# PSPS_AVNC_SRD_central-2020-10-21_FABRICA.net
KiCad netlist of a schematic drawn in EAGLE
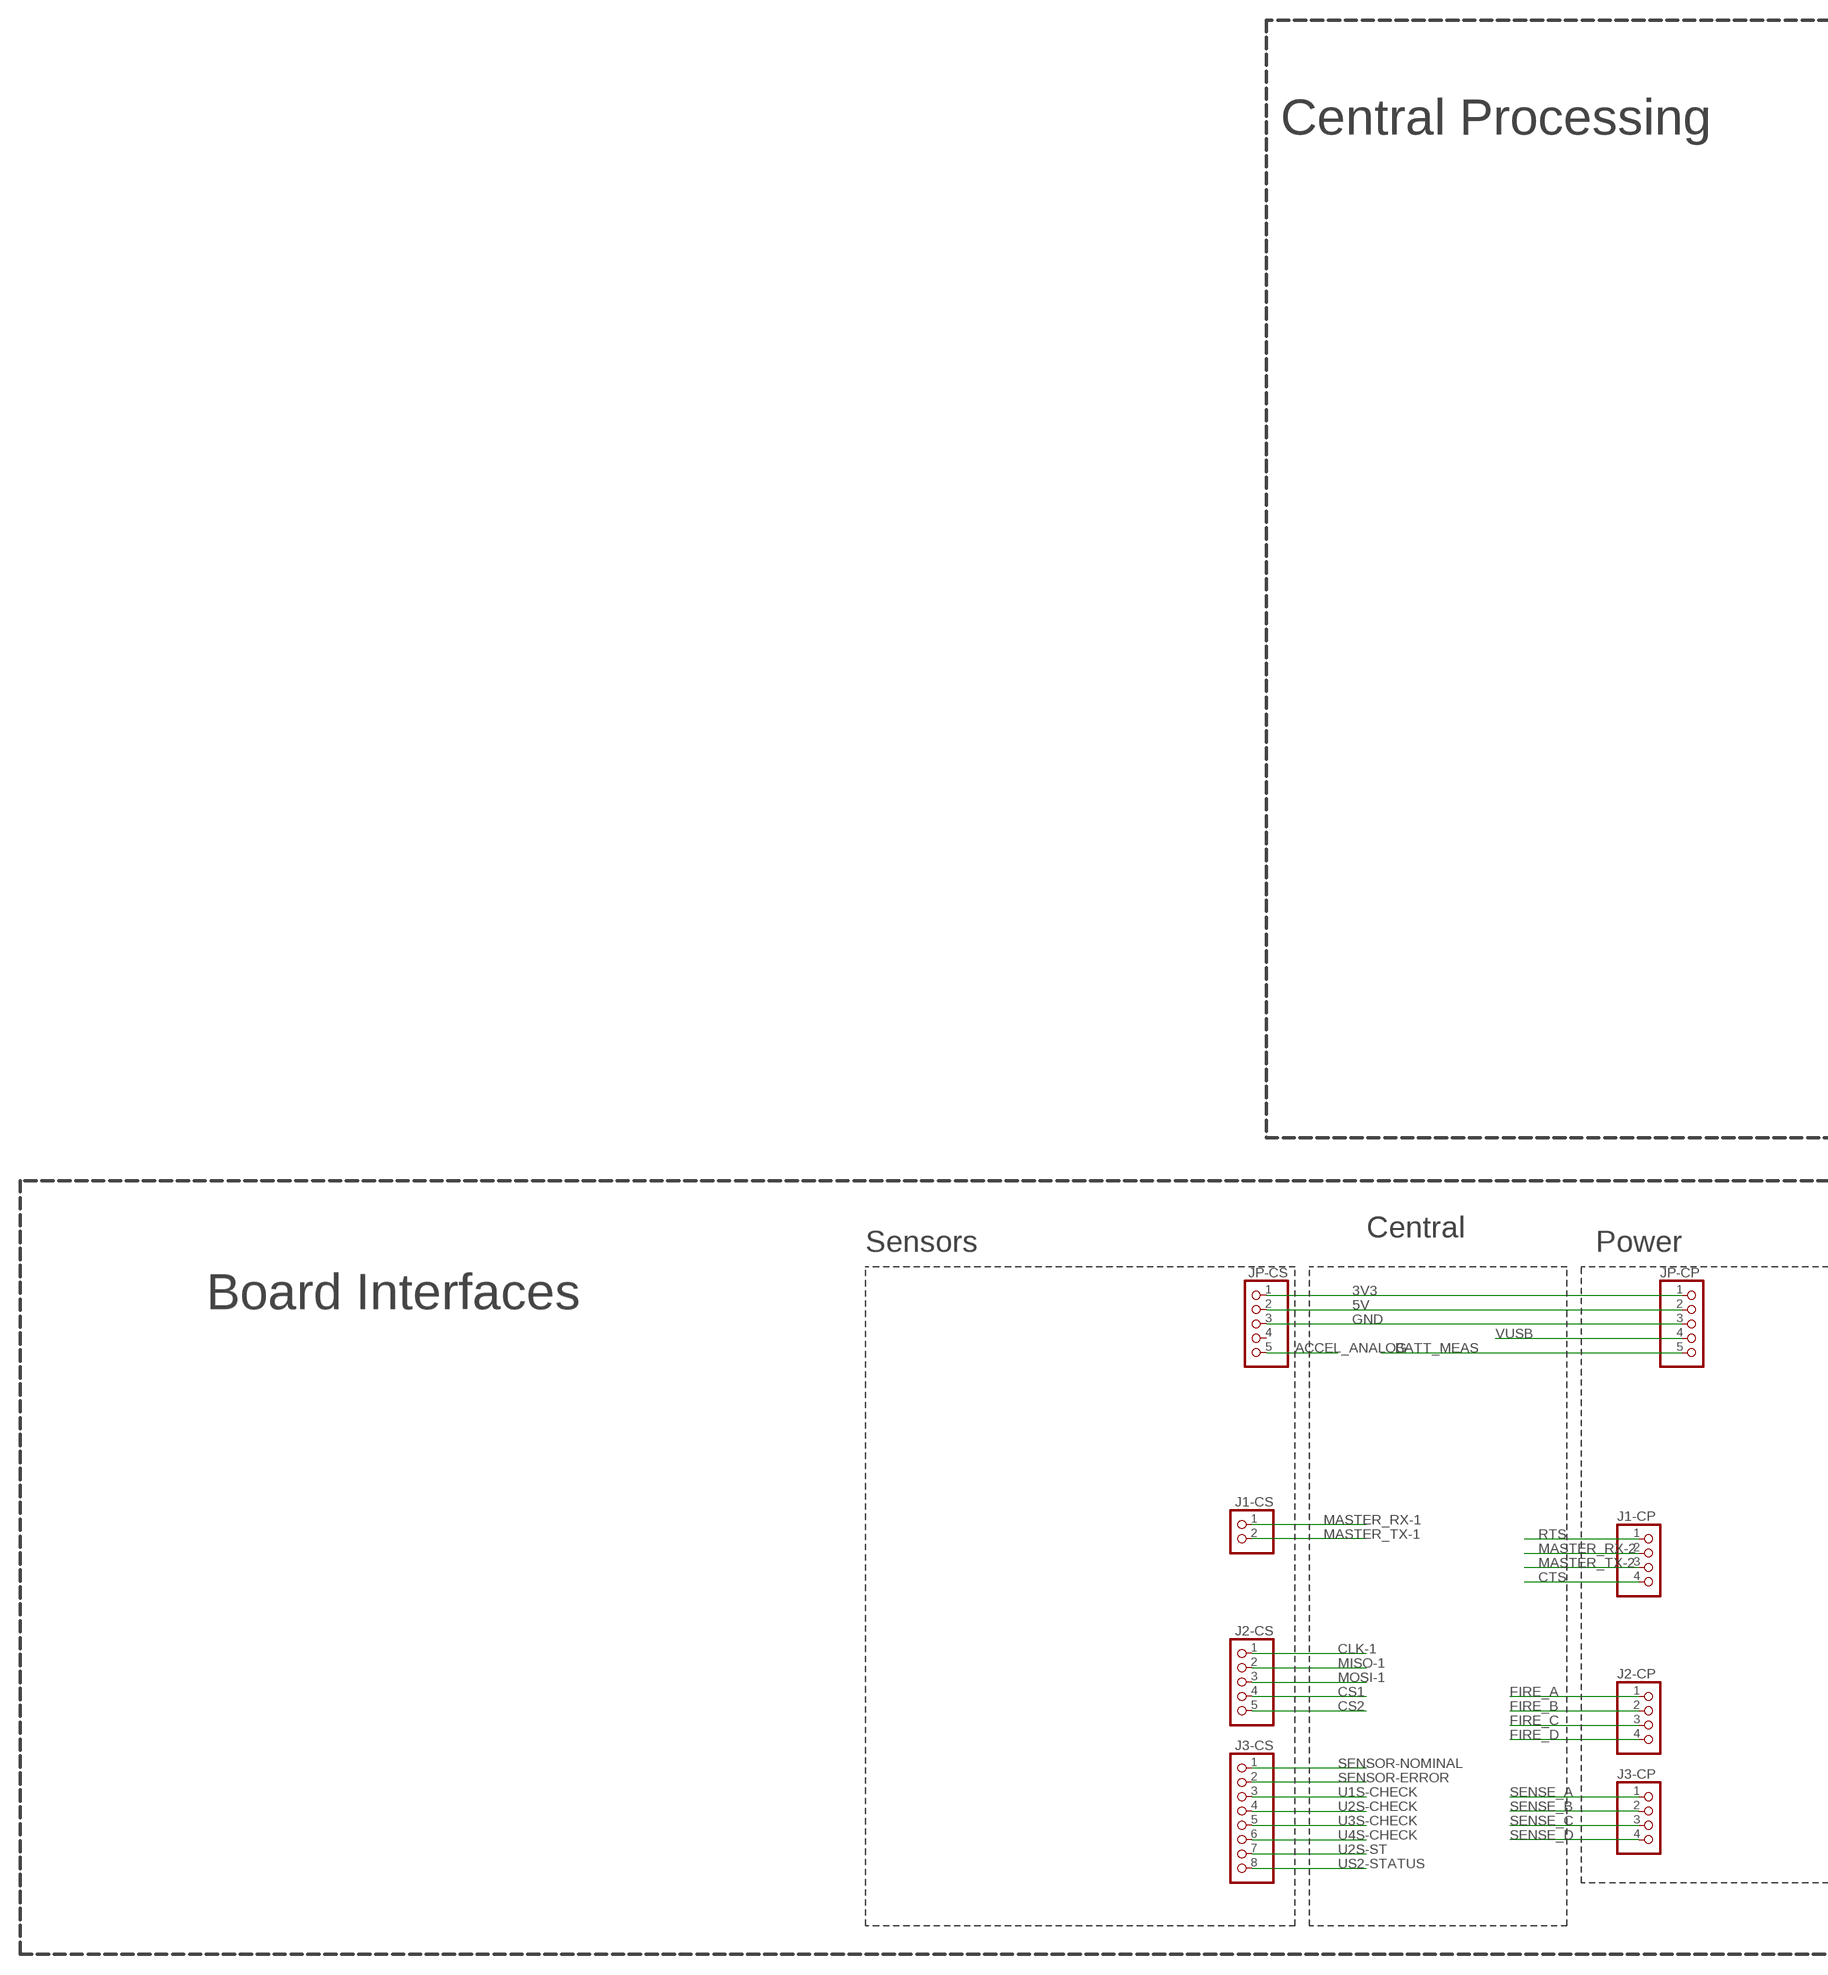
[diagram p0: schematic, sheet 1, part 1 of 2]
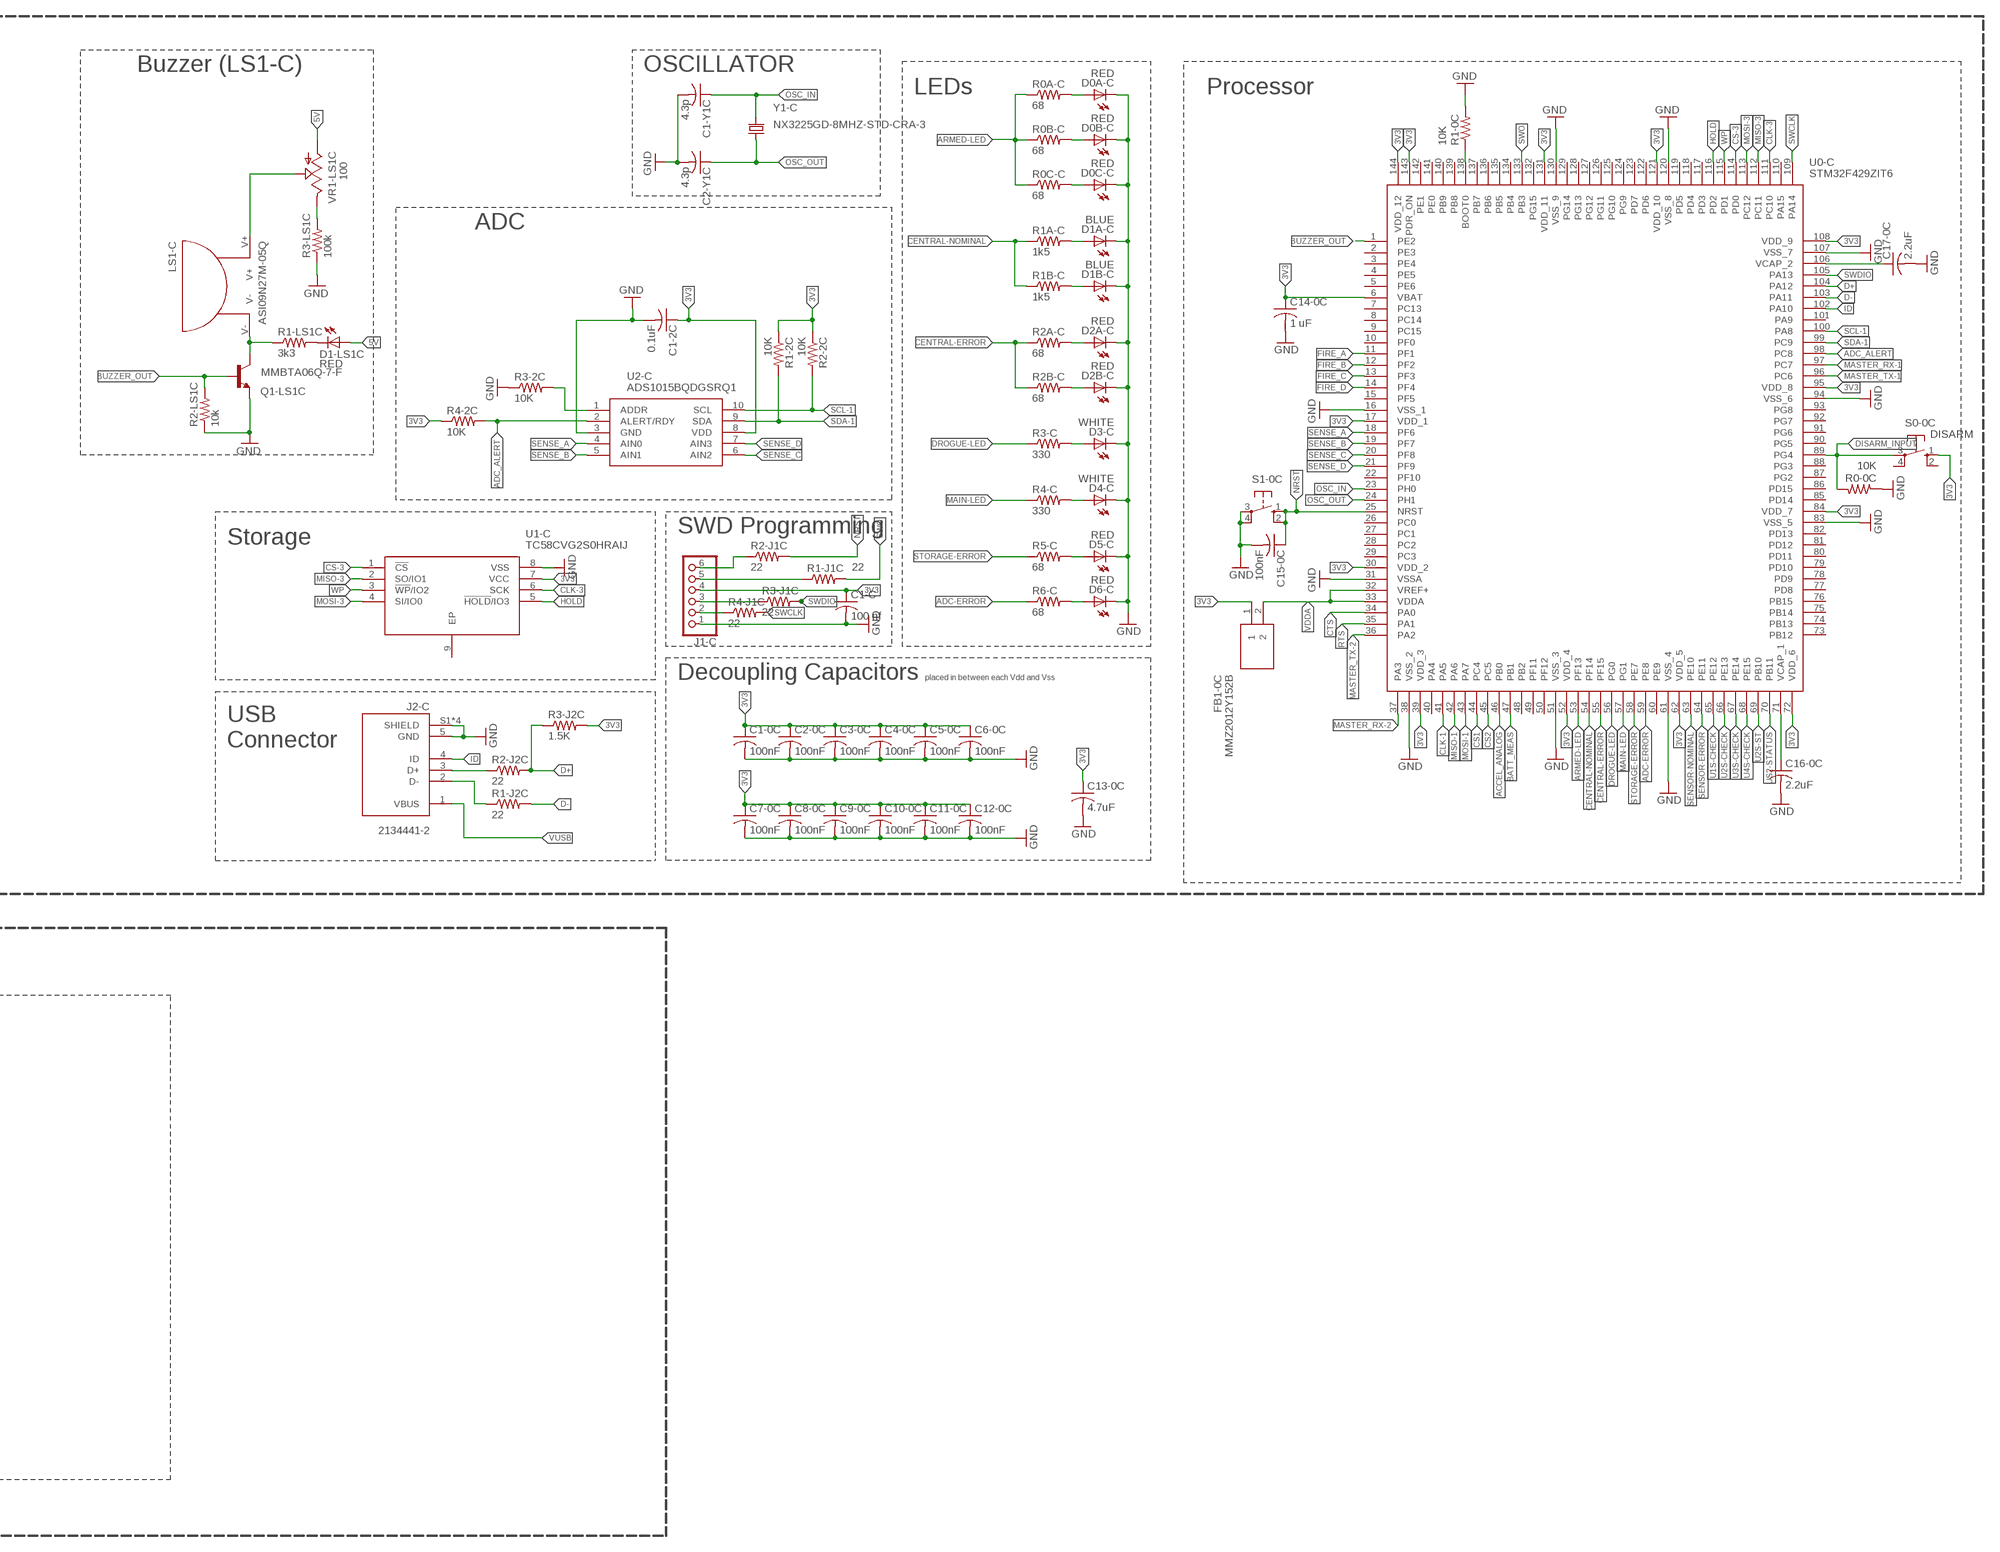
[diagram p1: schematic, sheet 1, part 2 of 2]

(export (version "E")
  (design (tool "Eeschema 10.0.6"))
  (components
    (comp (ref "C1-0C")
      (value "100nF")
      (footprint "eagle-import:C0805")
      (libsource (lib "eagle-import") (part "C-USC0805"))
    )
    (comp (ref "C1-2C")
      (value "0.1uF")
      (footprint "eagle-import:C0805")
      (libsource (lib "eagle-import") (part "C-USC0805"))
    )
    (comp (ref "C1-C")
      (value "100 nf")
      (footprint "eagle-import:C0805")
      (libsource (lib "eagle-import") (part "C-USC0805"))
    )
    (comp (ref "C1-Y1C")
      (value "4.3p")
      (footprint "eagle-import:C0805")
      (libsource (lib "eagle-import") (part "C-USC0805"))
    )
    (comp (ref "C2-0C")
      (value "100nF")
      (footprint "eagle-import:C0805")
      (libsource (lib "eagle-import") (part "C-USC0805"))
    )
    (comp (ref "C2-Y1C")
      (value "4.3p")
      (footprint "eagle-import:C0805")
      (libsource (lib "eagle-import") (part "C-USC0805"))
    )
    (comp (ref "C3-0C")
      (value "100nF")
      (footprint "eagle-import:C0805")
      (libsource (lib "eagle-import") (part "C-USC0805"))
    )
    (comp (ref "C4-0C")
      (value "100nF")
      (footprint "eagle-import:C0805")
      (libsource (lib "eagle-import") (part "C-USC0805"))
    )
    (comp (ref "C5-0C")
      (value "100nF")
      (footprint "eagle-import:C0805")
      (libsource (lib "eagle-import") (part "C-USC0805"))
    )
    (comp (ref "C6-0C")
      (value "100nF")
      (footprint "eagle-import:C0805")
      (libsource (lib "eagle-import") (part "C-USC0805"))
    )
    (comp (ref "C7-0C")
      (value "100nF")
      (footprint "eagle-import:C0805")
      (libsource (lib "eagle-import") (part "C-USC0805"))
    )
    (comp (ref "C8-0C")
      (value "100nF")
      (footprint "eagle-import:C0805")
      (libsource (lib "eagle-import") (part "C-USC0805"))
    )
    (comp (ref "C9-0C")
      (value "100nF")
      (footprint "eagle-import:C0805")
      (libsource (lib "eagle-import") (part "C-USC0805"))
    )
    (comp (ref "C10-0C")
      (value "100nF")
      (footprint "eagle-import:C0805")
      (libsource (lib "eagle-import") (part "C-USC0805"))
    )
    (comp (ref "C11-0C")
      (value "100nF")
      (footprint "eagle-import:C0805")
      (libsource (lib "eagle-import") (part "C-USC0805"))
    )
    (comp (ref "C12-0C")
      (value "100nF")
      (footprint "eagle-import:C0805")
      (libsource (lib "eagle-import") (part "C-USC0805"))
    )
    (comp (ref "C13-0C")
      (value "4.7uF")
      (footprint "eagle-import:C0805")
      (libsource (lib "eagle-import") (part "C-USC0805"))
    )
    (comp (ref "C14-0C")
      (value "1 uF")
      (footprint "eagle-import:C0805")
      (libsource (lib "eagle-import") (part "C-USC0805"))
    )
    (comp (ref "C15-0C")
      (value "100nF")
      (footprint "eagle-import:C0805")
      (libsource (lib "eagle-import") (part "C-USC0805"))
    )
    (comp (ref "C16-0C")
      (value "2.2uF")
      (footprint "eagle-import:C0805")
      (libsource (lib "eagle-import") (part "C-USC0805"))
    )
    (comp (ref "C17-0C")
      (value "2.2uF")
      (footprint "eagle-import:C0805")
      (libsource (lib "eagle-import") (part "C-USC0805"))
    )
    (comp (ref "D0A-C")
      (value "RED")
      (footprint "eagle-import:CHIPLED_0805")
      (libsource (lib "eagle-import") (part "LEDCHIPLED_0805"))
    )
    (comp (ref "D0B-C")
      (value "RED")
      (footprint "eagle-import:CHIPLED_0805")
      (libsource (lib "eagle-import") (part "LEDCHIPLED_0805"))
    )
    (comp (ref "D0C-C")
      (value "RED")
      (footprint "eagle-import:CHIPLED_0805")
      (libsource (lib "eagle-import") (part "LEDCHIPLED_0805"))
    )
    (comp (ref "D1-LS1C")
      (value "RED")
      (footprint "eagle-import:CHIPLED_0805")
      (libsource (lib "eagle-import") (part "LEDCHIPLED_0805"))
    )
    (comp (ref "D1A-C")
      (value "BLUE")
      (footprint "eagle-import:CHIPLED_0805")
      (libsource (lib "eagle-import") (part "LEDCHIPLED_0805"))
    )
    (comp (ref "D1B-C")
      (value "BLUE")
      (footprint "eagle-import:CHIPLED_0805")
      (libsource (lib "eagle-import") (part "LEDCHIPLED_0805"))
    )
    (comp (ref "D2A-C")
      (value "RED")
      (footprint "eagle-import:CHIPLED_0805")
      (libsource (lib "eagle-import") (part "LEDCHIPLED_0805"))
    )
    (comp (ref "D2B-C")
      (value "RED")
      (footprint "eagle-import:CHIPLED_0805")
      (libsource (lib "eagle-import") (part "LEDCHIPLED_0805"))
    )
    (comp (ref "D3-C")
      (value "WHITE")
      (footprint "eagle-import:CHIPLED_0805")
      (libsource (lib "eagle-import") (part "LEDCHIPLED_0805"))
    )
    (comp (ref "D4-C")
      (value "WHITE")
      (footprint "eagle-import:CHIPLED_0805")
      (libsource (lib "eagle-import") (part "LEDCHIPLED_0805"))
    )
    (comp (ref "D5-C")
      (value "RED")
      (footprint "eagle-import:CHIPLED_0805")
      (libsource (lib "eagle-import") (part "LEDCHIPLED_0805"))
    )
    (comp (ref "D6-C")
      (value "RED")
      (footprint "eagle-import:CHIPLED_0805")
      (libsource (lib "eagle-import") (part "LEDCHIPLED_0805"))
    )
    (comp (ref "FB1-0C")
      (value "MMZ2012Y152B")
      (footprint "eagle-import:BEADC2012X105N")
      (fields (field (name "MOUSER_PART_NUMBER") "810-MMZ2012Y152B"))
      (libsource (lib "eagle-import") (part "MMZ2012Y152B"))
    )
    (comp (ref "J1-C")
      (value "PINHD-1X6")
      (footprint "eagle-import:1X06")
      (libsource (lib "eagle-import") (part "PINHD-1X6"))
    )
    (comp (ref "J1-CP")
      (value "PINHD-1X4")
      (footprint "eagle-import:1X04")
      (libsource (lib "eagle-import") (part "PINHD-1X4"))
    )
    (comp (ref "J1-CS")
      (value "PINHD-1X2")
      (footprint "eagle-import:1X02")
      (libsource (lib "eagle-import") (part "PINHD-1X2"))
    )
    (comp (ref "J2-C")
      (value "2134441-2")
      (footprint "eagle-import:TE_2134441-2")
      (fields (field (name "DIGI-KEY_PART_NUMBER") "A118104CT-ND") (field (name "MF") "TE Connectivity"))
      (libsource (lib "eagle-import") (part "2134441-2"))
    )
    (comp (ref "J2-CP")
      (value "PINHD-1X4")
      (footprint "eagle-import:1X04")
      (libsource (lib "eagle-import") (part "PINHD-1X4"))
    )
    (comp (ref "J2-CS")
      (value "PINHD-1X5")
      (footprint "eagle-import:1X05")
      (libsource (lib "eagle-import") (part "PINHD-1X5"))
    )
    (comp (ref "J3-CP")
      (value "PINHD-1X4")
      (footprint "eagle-import:1X04")
      (libsource (lib "eagle-import") (part "PINHD-1X4"))
    )
    (comp (ref "J3-CS")
      (value "PINHD-1X8")
      (footprint "eagle-import:1X08")
      (libsource (lib "eagle-import") (part "PINHD-1X8"))
    )
    (comp (ref "JP-CP")
      (value "PINHD-1X5")
      (footprint "eagle-import:1X05")
      (libsource (lib "eagle-import") (part "PINHD-1X5"))
    )
    (comp (ref "JP-CS")
      (value "PINHD-1X5")
      (footprint "eagle-import:1X05")
      (libsource (lib "eagle-import") (part "PINHD-1X5"))
    )
    (comp (ref "LS1-C")
      (value "ASI09N27M-05Q")
      (footprint "eagle-import:ASI09N27M-05Q")
      (libsource (lib "eagle-import") (part "ASI09N27M-05Q"))
    )
    (comp (ref "Q1-LS1C")
      (value "MMBTA06Q-7-F")
      (footprint "eagle-import:SOT23")
      (libsource (lib "eagle-import") (part "NPN_TRANSISTOR"))
    )
    (comp (ref "R0-0C")
      (value "10K")
      (footprint "eagle-import:R0805")
      (libsource (lib "eagle-import") (part "R-US_R0805"))
    )
    (comp (ref "R0A-C")
      (value "68")
      (footprint "eagle-import:M0805")
      (libsource (lib "eagle-import") (part "R-US_M0805"))
    )
    (comp (ref "R0B-C")
      (value "68")
      (footprint "eagle-import:M0805")
      (libsource (lib "eagle-import") (part "R-US_M0805"))
    )
    (comp (ref "R0C-C")
      (value "68")
      (footprint "eagle-import:M0805")
      (libsource (lib "eagle-import") (part "R-US_M0805"))
    )
    (comp (ref "R1-0C")
      (value "10K")
      (footprint "eagle-import:R0805")
      (libsource (lib "eagle-import") (part "R-US_R0805"))
    )
    (comp (ref "R1-2C")
      (value "10K")
      (footprint "eagle-import:R0805")
      (libsource (lib "eagle-import") (part "R-US_R0805"))
    )
    (comp (ref "R1-J1C")
      (value "22")
      (footprint "eagle-import:M0805")
      (libsource (lib "eagle-import") (part "R-US_M0805"))
    )
    (comp (ref "R1-J2C")
      (value "22")
      (footprint "eagle-import:M0805")
      (libsource (lib "eagle-import") (part "R-US_M0805"))
    )
    (comp (ref "R1-LS1C")
      (value "3k3")
      (footprint "eagle-import:R0805")
      (libsource (lib "eagle-import") (part "resistor_348_R-US_R0805"))
    )
    (comp (ref "R1A-C")
      (value "1k5")
      (footprint "eagle-import:M0805")
      (libsource (lib "eagle-import") (part "R-US_M0805"))
    )
    (comp (ref "R1B-C")
      (value "1k5")
      (footprint "eagle-import:M0805")
      (libsource (lib "eagle-import") (part "R-US_M0805"))
    )
    (comp (ref "R2-2C")
      (value "10K")
      (footprint "eagle-import:R0805")
      (libsource (lib "eagle-import") (part "R-US_R0805"))
    )
    (comp (ref "R2-J1C")
      (value "22")
      (footprint "eagle-import:M0805")
      (libsource (lib "eagle-import") (part "R-US_M0805"))
    )
    (comp (ref "R2-J2C")
      (value "22")
      (footprint "eagle-import:M0805")
      (libsource (lib "eagle-import") (part "R-US_M0805"))
    )
    (comp (ref "R2-LS1C")
      (value "10k")
      (footprint "eagle-import:R0805")
      (libsource (lib "eagle-import") (part "resistor_348_R-US_R0805"))
    )
    (comp (ref "R2A-C")
      (value "68")
      (footprint "eagle-import:M0805")
      (libsource (lib "eagle-import") (part "R-US_M0805"))
    )
    (comp (ref "R2B-C")
      (value "68")
      (footprint "eagle-import:M0805")
      (libsource (lib "eagle-import") (part "R-US_M0805"))
    )
    (comp (ref "R3-2C")
      (value "10K")
      (footprint "eagle-import:R0805")
      (libsource (lib "eagle-import") (part "R-US_R0805"))
    )
    (comp (ref "R3-C")
      (value "330")
      (footprint "eagle-import:M0805")
      (libsource (lib "eagle-import") (part "R-US_M0805"))
    )
    (comp (ref "R3-J1C")
      (value "22")
      (footprint "eagle-import:M0805")
      (libsource (lib "eagle-import") (part "R-US_M0805"))
    )
    (comp (ref "R3-J2C")
      (value "1.5K")
      (footprint "eagle-import:M0805")
      (libsource (lib "eagle-import") (part "R-US_M0805"))
    )
    (comp (ref "R3-LS1C")
      (value "100k")
      (footprint "eagle-import:R0805")
      (libsource (lib "eagle-import") (part "resistor_348_R-US_R0805"))
    )
    (comp (ref "R4-2C")
      (value "10K")
      (footprint "eagle-import:R0805")
      (libsource (lib "eagle-import") (part "R-US_R0805"))
    )
    (comp (ref "R4-C")
      (value "330")
      (footprint "eagle-import:M0805")
      (libsource (lib "eagle-import") (part "R-US_M0805"))
    )
    (comp (ref "R4-J1C")
      (value "22")
      (footprint "eagle-import:M0805")
      (libsource (lib "eagle-import") (part "R-US_M0805"))
    )
    (comp (ref "R5-C")
      (value "68")
      (footprint "eagle-import:M0805")
      (libsource (lib "eagle-import") (part "R-US_M0805"))
    )
    (comp (ref "R6-C")
      (value "68")
      (footprint "eagle-import:M0805")
      (libsource (lib "eagle-import") (part "R-US_M0805"))
    )
    (comp (ref "S0-0C")
      (value "DISARM")
      (footprint "eagle-import:B3F-10XX")
      (fields (field (name "MPN") "B3F-1000"))
      (libsource (lib "eagle-import") (part "10-XX"))
    )
    (comp (ref "S1-0C")
      (value "10-XX")
      (footprint "eagle-import:B3F-10XX")
      (fields (field (name "MPN") "B3F-1000"))
      (libsource (lib "eagle-import") (part "10-XX"))
    )
    (comp (ref "U0-C")
      (value "STM32F429ZIT6")
      (footprint "eagle-import:QFP50P2200X2200X160-144N")
      (fields (field (name "MOUSER_PART_NUMBER") "511-STM32F429ZIT6"))
      (libsource (lib "eagle-import") (part "STM32F429ZIT6"))
    )
    (comp (ref "U1-C")
      (value "TC58CVG2S0HRAIJ")
      (footprint "eagle-import:SON127P800X600X80-9N")
      (fields (field (name "MOUSER_PART_NUMBER") "757-TC58CVG2S0HRAIJ"))
      (libsource (lib "eagle-import") (part "TC58CVG2S0HRAIJ"))
    )
    (comp (ref "U2-C")
      (value "ADS1015BQDGSRQ1")
      (footprint "eagle-import:SOP50P490X110-10N")
      (fields (field (name "MOUSER_PART_NUMBER") "595-ADS1015BQDGSRQ1"))
      (libsource (lib "eagle-import") (part "ADS1015BQDGSRQ1"))
    )
    (comp (ref "VR1-LS1C")
      (value "100")
      (footprint "eagle-import:LI10")
      (libsource (lib "eagle-import") (part "TRIM_US-LI10"))
    )
    (comp (ref "Y1-C")
      (value "NX3225GD-8MHZ-STD-CRA-3")
      (footprint "eagle-import:NX3225GD")
      (libsource (lib "eagle-import") (part "NX3225GD"))
    )
  )
  (nets
    (net (code "1") (name "3V3") (class "Default")
      (node (ref "C1-0C") (pin "1") (pinfunction "1_1") (pintype "passive"))
      (node (ref "C1-2C") (pin "1") (pinfunction "1_1") (pintype "passive"))
      (node (ref "C1-C") (pin "1") (pinfunction "1_1") (pintype "passive"))
      (node (ref "C10-0C") (pin "1") (pinfunction "1_1") (pintype "passive"))
      (node (ref "C11-0C") (pin "1") (pinfunction "1_1") (pintype "passive"))
      (node (ref "C12-0C") (pin "1") (pinfunction "1_1") (pintype "passive"))
      (node (ref "C13-0C") (pin "1") (pinfunction "1_1") (pintype "passive"))
      (node (ref "C14-0C") (pin "1") (pinfunction "1_1") (pintype "passive"))
      (node (ref "C2-0C") (pin "1") (pinfunction "1_1") (pintype "passive"))
      (node (ref "C3-0C") (pin "1") (pinfunction "1_1") (pintype "passive"))
      (node (ref "C4-0C") (pin "1") (pinfunction "1_1") (pintype "passive"))
      (node (ref "C5-0C") (pin "1") (pinfunction "1_1") (pintype "passive"))
      (node (ref "C6-0C") (pin "1") (pinfunction "1_1") (pintype "passive"))
      (node (ref "C7-0C") (pin "1") (pinfunction "1_1") (pintype "passive"))
      (node (ref "C8-0C") (pin "1") (pinfunction "1_1") (pintype "passive"))
      (node (ref "C9-0C") (pin "1") (pinfunction "1_1") (pintype "passive"))
      (node (ref "FB1-0C") (pin "1") (pinfunction "1_1") (pintype "bidirectional"))
      (node (ref "J1-C") (pin "4") (pinfunction "4_4") (pintype "passive"))
      (node (ref "JP-CP") (pin "1") (pinfunction "1_1") (pintype "passive"))
      (node (ref "JP-CS") (pin "1") (pinfunction "1_1") (pintype "passive"))
      (node (ref "R1-2C") (pin "1") (pinfunction "1_1") (pintype "passive"))
      (node (ref "R2-2C") (pin "1") (pinfunction "1_1") (pintype "passive"))
      (node (ref "R3-J2C") (pin "2") (pinfunction "2_2") (pintype "passive"))
      (node (ref "R4-2C") (pin "1") (pinfunction "1_1") (pintype "passive"))
      (node (ref "S0-0C") (pin "1") (pinfunction "S_1") (pintype "passive"))
      (node (ref "U0-C") (pin "108") (pinfunction "VDD_9_108") (pintype "power_in"))
      (node (ref "U0-C") (pin "121") (pinfunction "VDD_10_121") (pintype "power_in"))
      (node (ref "U0-C") (pin "131") (pinfunction "VDD_11_131") (pintype "power_in"))
      (node (ref "U0-C") (pin "143") (pinfunction "PDR_ON_143") (pintype "bidirectional"))
      (node (ref "U0-C") (pin "144") (pinfunction "VDD_12_144") (pintype "power_in"))
      (node (ref "U0-C") (pin "17") (pinfunction "VDD_1_17") (pintype "power_in"))
      (node (ref "U0-C") (pin "30") (pinfunction "VDD_2_30") (pintype "power_in"))
      (node (ref "U0-C") (pin "39") (pinfunction "VDD_3_39") (pintype "power_in"))
      (node (ref "U0-C") (pin "52") (pinfunction "VDD_4_52") (pintype "power_in"))
      (node (ref "U0-C") (pin "6") (pinfunction "VBAT_6") (pintype "bidirectional"))
      (node (ref "U0-C") (pin "62") (pinfunction "VDD_5_62") (pintype "power_in"))
      (node (ref "U0-C") (pin "72") (pinfunction "VDD_6_72") (pintype "power_in"))
      (node (ref "U0-C") (pin "84") (pinfunction "VDD_7_84") (pintype "power_in"))
      (node (ref "U0-C") (pin "95") (pinfunction "VDD_8_95") (pintype "power_in"))
      (node (ref "U1-C") (pin "7") (pinfunction "VCC_7") (pintype "bidirectional"))
      (node (ref "U2-C") (pin "8") (pinfunction "VDD_8") (pintype "bidirectional"))
    )
    (net (code "2") (name "5V") (class "Default")
      (node (ref "D1-LS1C") (pin "A") (pinfunction "A_A") (pintype "passive"))
      (node (ref "JP-CP") (pin "2") (pinfunction "2_2") (pintype "passive"))
      (node (ref "JP-CS") (pin "2") (pinfunction "2_2") (pintype "passive"))
      (node (ref "VR1-LS1C") (pin "A") (pinfunction "A_A") (pintype "passive"))
    )
    (net (code "3") (name "ACCEL_ANALOG") (class "Default")
      (node (ref "JP-CS") (pin "5") (pinfunction "5_5") (pintype "passive"))
      (node (ref "U0-C") (pin "46") (pinfunction "PB0_46") (pintype "bidirectional"))
    )
    (net (code "4") (name "ADC-ERROR") (class "Default")
      (node (ref "R6-C") (pin "1") (pinfunction "1_1") (pintype "passive"))
      (node (ref "U0-C") (pin "59") (pinfunction "PE8_59") (pintype "bidirectional"))
    )
    (net (code "5") (name "ADC_ALERT") (class "Default")
      (node (ref "R4-2C") (pin "2") (pinfunction "2_2") (pintype "passive"))
      (node (ref "U0-C") (pin "98") (pinfunction "PC8_98") (pintype "bidirectional"))
      (node (ref "U2-C") (pin "2") (pinfunction "ALERT/RDY_2") (pintype "bidirectional"))
    )
    (net (code "6") (name "ARMED-LED") (class "Default")
      (node (ref "R0A-C") (pin "1") (pinfunction "1_1") (pintype "passive"))
      (node (ref "R0B-C") (pin "1") (pinfunction "1_1") (pintype "passive"))
      (node (ref "R0C-C") (pin "1") (pinfunction "1_1") (pintype "passive"))
      (node (ref "U0-C") (pin "53") (pinfunction "PF13_53") (pintype "bidirectional"))
    )
    (net (code "7") (name "BATT_MEAS") (class "Default")
      (node (ref "JP-CP") (pin "5") (pinfunction "5_5") (pintype "passive"))
      (node (ref "U0-C") (pin "47") (pinfunction "PB1_47") (pintype "bidirectional"))
    )
    (net (code "8") (name "BUZZER_OUT") (class "Default")
      (node (ref "Q1-LS1C") (pin "1") (pinfunction "B_1") (pintype "passive"))
      (node (ref "R2-LS1C") (pin "2") (pinfunction "2_2") (pintype "passive"))
      (node (ref "U0-C") (pin "1") (pinfunction "PE2_1") (pintype "bidirectional"))
    )
    (net (code "9") (name "CENTRAL-ERROR") (class "Default")
      (node (ref "R2A-C") (pin "1") (pinfunction "1_1") (pintype "passive"))
      (node (ref "R2B-C") (pin "1") (pinfunction "1_1") (pintype "passive"))
      (node (ref "U0-C") (pin "55") (pinfunction "PF15_55") (pintype "bidirectional"))
    )
    (net (code "10") (name "CENTRAL-NOMINAL") (class "Default")
      (node (ref "R1A-C") (pin "1") (pinfunction "1_1") (pintype "passive"))
      (node (ref "R1B-C") (pin "1") (pinfunction "1_1") (pintype "passive"))
      (node (ref "U0-C") (pin "54") (pinfunction "PF14_54") (pintype "bidirectional"))
    )
    (net (code "11") (name "CLK-1") (class "Default")
      (node (ref "J2-CS") (pin "1") (pinfunction "1_1") (pintype "passive"))
      (node (ref "U0-C") (pin "41") (pinfunction "PA5_41") (pintype "bidirectional"))
    )
    (net (code "12") (name "CLK-3") (class "Default")
      (node (ref "U0-C") (pin "111") (pinfunction "PC10_111") (pintype "bidirectional"))
      (node (ref "U1-C") (pin "6") (pinfunction "SCK_6") (pintype "bidirectional"))
    )
    (net (code "13") (name "CS-3") (class "Default")
      (node (ref "U0-C") (pin "114") (pinfunction "PD0_114") (pintype "bidirectional"))
      (node (ref "U1-C") (pin "1") (pinfunction "~{CS}_1") (pintype "bidirectional"))
    )
    (net (code "14") (name "CS1") (class "Default")
      (node (ref "J2-CS") (pin "4") (pinfunction "4_4") (pintype "passive"))
      (node (ref "U0-C") (pin "44") (pinfunction "PC4_44") (pintype "bidirectional"))
    )
    (net (code "15") (name "CS2") (class "Default")
      (node (ref "J2-CS") (pin "5") (pinfunction "5_5") (pintype "passive"))
      (node (ref "U0-C") (pin "45") (pinfunction "PC5_45") (pintype "bidirectional"))
    )
    (net (code "16") (name "CTS") (class "Default")
      (node (ref "J1-CP") (pin "4") (pinfunction "4_4") (pintype "passive"))
      (node (ref "U0-C") (pin "34") (pinfunction "PA0_34") (pintype "bidirectional"))
    )
    (net (code "17") (name "D+") (class "Default")
      (node (ref "R2-J2C") (pin "2") (pinfunction "2_2") (pintype "passive"))
      (node (ref "R3-J2C") (pin "1") (pinfunction "1_1") (pintype "passive"))
      (node (ref "U0-C") (pin "104") (pinfunction "PA12_104") (pintype "bidirectional"))
    )
    (net (code "18") (name "D-") (class "Default")
      (node (ref "R1-J2C") (pin "2") (pinfunction "2_2") (pintype "passive"))
      (node (ref "U0-C") (pin "103") (pinfunction "PA11_103") (pintype "bidirectional"))
    )
    (net (code "19") (name "DISARM_INPUT") (class "Default")
      (node (ref "R0-0C") (pin "2") (pinfunction "2_2") (pintype "passive"))
      (node (ref "S0-0C") (pin "3") (pinfunction "P_3") (pintype "passive"))
      (node (ref "U0-C") (pin "89") (pinfunction "PG4_89") (pintype "bidirectional"))
    )
    (net (code "20") (name "DROGUE-LED") (class "Default")
      (node (ref "R3-C") (pin "1") (pinfunction "1_1") (pintype "passive"))
      (node (ref "U0-C") (pin "56") (pinfunction "PG0_56") (pintype "bidirectional"))
    )
    (net (code "21") (name "FIRE_A") (class "Default")
      (node (ref "J2-CP") (pin "1") (pinfunction "1_1") (pintype "passive"))
      (node (ref "U0-C") (pin "11") (pinfunction "PF1_11") (pintype "bidirectional"))
    )
    (net (code "22") (name "FIRE_B") (class "Default")
      (node (ref "J2-CP") (pin "2") (pinfunction "2_2") (pintype "passive"))
      (node (ref "U0-C") (pin "12") (pinfunction "PF2_12") (pintype "bidirectional"))
    )
    (net (code "23") (name "FIRE_C") (class "Default")
      (node (ref "J2-CP") (pin "3") (pinfunction "3_3") (pintype "passive"))
      (node (ref "U0-C") (pin "13") (pinfunction "PF3_13") (pintype "bidirectional"))
    )
    (net (code "24") (name "FIRE_D") (class "Default")
      (node (ref "J2-CP") (pin "4") (pinfunction "4_4") (pintype "passive"))
      (node (ref "U0-C") (pin "14") (pinfunction "PF4_14") (pintype "bidirectional"))
    )
    (net (code "25") (name "GND") (class "Default")
      (node (ref "C1-0C") (pin "2") (pinfunction "2_2") (pintype "passive"))
      (node (ref "C1-2C") (pin "2") (pinfunction "2_2") (pintype "passive"))
      (node (ref "C1-C") (pin "2") (pinfunction "2_2") (pintype "passive"))
      (node (ref "C1-Y1C") (pin "2") (pinfunction "2_2") (pintype "passive"))
      (node (ref "C10-0C") (pin "2") (pinfunction "2_2") (pintype "passive"))
      (node (ref "C11-0C") (pin "2") (pinfunction "2_2") (pintype "passive"))
      (node (ref "C12-0C") (pin "2") (pinfunction "2_2") (pintype "passive"))
      (node (ref "C13-0C") (pin "2") (pinfunction "2_2") (pintype "passive"))
      (node (ref "C14-0C") (pin "2") (pinfunction "2_2") (pintype "passive"))
      (node (ref "C15-0C") (pin "2") (pinfunction "2_2") (pintype "passive"))
      (node (ref "C16-0C") (pin "2") (pinfunction "2_2") (pintype "passive"))
      (node (ref "C17-0C") (pin "2") (pinfunction "2_2") (pintype "passive"))
      (node (ref "C2-0C") (pin "2") (pinfunction "2_2") (pintype "passive"))
      (node (ref "C2-Y1C") (pin "2") (pinfunction "2_2") (pintype "passive"))
      (node (ref "C3-0C") (pin "2") (pinfunction "2_2") (pintype "passive"))
      (node (ref "C4-0C") (pin "2") (pinfunction "2_2") (pintype "passive"))
      (node (ref "C5-0C") (pin "2") (pinfunction "2_2") (pintype "passive"))
      (node (ref "C6-0C") (pin "2") (pinfunction "2_2") (pintype "passive"))
      (node (ref "C7-0C") (pin "2") (pinfunction "2_2") (pintype "passive"))
      (node (ref "C8-0C") (pin "2") (pinfunction "2_2") (pintype "passive"))
      (node (ref "C9-0C") (pin "2") (pinfunction "2_2") (pintype "passive"))
      (node (ref "D0A-C") (pin "C") (pinfunction "C_C") (pintype "passive"))
      (node (ref "D0B-C") (pin "C") (pinfunction "C_C") (pintype "passive"))
      (node (ref "D0C-C") (pin "C") (pinfunction "C_C") (pintype "passive"))
      (node (ref "D1A-C") (pin "C") (pinfunction "C_C") (pintype "passive"))
      (node (ref "D1B-C") (pin "C") (pinfunction "C_C") (pintype "passive"))
      (node (ref "D2A-C") (pin "C") (pinfunction "C_C") (pintype "passive"))
      (node (ref "D2B-C") (pin "C") (pinfunction "C_C") (pintype "passive"))
      (node (ref "D3-C") (pin "C") (pinfunction "C_C") (pintype "passive"))
      (node (ref "D4-C") (pin "C") (pinfunction "C_C") (pintype "passive"))
      (node (ref "D5-C") (pin "C") (pinfunction "C_C") (pintype "passive"))
      (node (ref "D6-C") (pin "C") (pinfunction "C_C") (pintype "passive"))
      (node (ref "J1-C") (pin "1") (pinfunction "1_1") (pintype "passive"))
      (node (ref "J2-C") (pin "5") (pinfunction "GND_5") (pintype "power_in"))
      (node (ref "J2-C") (pin "S1") (pinfunction "SHIELD_S1") (pintype "power_in"))
      (node (ref "J2-C") (pin "S2") (pinfunction "SHIELD_S2") (pintype "power_in"))
      (node (ref "J2-C") (pin "S3") (pinfunction "SHIELD_S3") (pintype "power_in"))
      (node (ref "J2-C") (pin "S4") (pinfunction "SHIELD_S4") (pintype "power_in"))
      (node (ref "JP-CP") (pin "3") (pinfunction "3_3") (pintype "passive"))
      (node (ref "JP-CS") (pin "3") (pinfunction "3_3") (pintype "passive"))
      (node (ref "Q1-LS1C") (pin "3") (pinfunction "E_3") (pintype "passive"))
      (node (ref "R0-0C") (pin "1") (pinfunction "1_1") (pintype "passive"))
      (node (ref "R1-0C") (pin "2") (pinfunction "2_2") (pintype "passive"))
      (node (ref "R2-LS1C") (pin "1") (pinfunction "1_1") (pintype "passive"))
      (node (ref "R3-2C") (pin "1") (pinfunction "1_1") (pintype "passive"))
      (node (ref "R3-LS1C") (pin "1") (pinfunction "1_1") (pintype "passive"))
      (node (ref "S1-0C") (pin "3") (pinfunction "P_3") (pintype "passive"))
      (node (ref "S1-0C") (pin "4") (pinfunction "P1_4") (pintype "passive"))
      (node (ref "U0-C") (pin "107") (pinfunction "VSS_7_107") (pintype "power_in"))
      (node (ref "U0-C") (pin "120") (pinfunction "VSS_8_120") (pintype "power_in"))
      (node (ref "U0-C") (pin "130") (pinfunction "VSS_9_130") (pintype "power_in"))
      (node (ref "U0-C") (pin "16") (pinfunction "VSS_1_16") (pintype "power_in"))
      (node (ref "U0-C") (pin "31") (pinfunction "VSSA_31") (pintype "power_in"))
      (node (ref "U0-C") (pin "38") (pinfunction "VSS_2_38") (pintype "power_in"))
      (node (ref "U0-C") (pin "51") (pinfunction "VSS_3_51") (pintype "power_in"))
      (node (ref "U0-C") (pin "61") (pinfunction "VSS_4_61") (pintype "power_in"))
      (node (ref "U0-C") (pin "83") (pinfunction "VSS_5_83") (pintype "power_in"))
      (node (ref "U0-C") (pin "94") (pinfunction "VSS_6_94") (pintype "power_in"))
      (node (ref "U1-C") (pin "8") (pinfunction "VSS_8") (pintype "bidirectional"))
      (node (ref "U2-C") (pin "3") (pinfunction "GND_3") (pintype "bidirectional"))
    )
    (net (code "26") (name "HOLD") (class "Default")
      (node (ref "U0-C") (pin "116") (pinfunction "PD2_116") (pintype "bidirectional"))
      (node (ref "U1-C") (pin "5") (pinfunction "~{HOLD}/IO3_5") (pintype "bidirectional"))
    )
    (net (code "27") (name "ID") (class "Default")
      (node (ref "J2-C") (pin "4") (pinfunction "ID_4") (pintype "bidirectional"))
      (node (ref "U0-C") (pin "102") (pinfunction "PA10_102") (pintype "bidirectional"))
    )
    (net (code "28") (name "MAIN-LED") (class "Default")
      (node (ref "R4-C") (pin "1") (pinfunction "1_1") (pintype "passive"))
      (node (ref "U0-C") (pin "57") (pinfunction "PG1_57") (pintype "bidirectional"))
    )
    (net (code "29") (name "MASTER_RX-1") (class "Default")
      (node (ref "J1-CS") (pin "1") (pinfunction "1_1") (pintype "passive"))
      (node (ref "U0-C") (pin "97") (pinfunction "PC7_97") (pintype "bidirectional"))
    )
    (net (code "30") (name "MASTER_RX-2") (class "Default")
      (node (ref "J1-CP") (pin "2") (pinfunction "2_2") (pintype "passive"))
      (node (ref "U0-C") (pin "37") (pinfunction "PA3_37") (pintype "bidirectional"))
    )
    (net (code "31") (name "MASTER_TX-1") (class "Default")
      (node (ref "J1-CS") (pin "2") (pinfunction "2_2") (pintype "passive"))
      (node (ref "U0-C") (pin "96") (pinfunction "PC6_96") (pintype "bidirectional"))
    )
    (net (code "32") (name "MASTER_TX-2") (class "Default")
      (node (ref "J1-CP") (pin "3") (pinfunction "3_3") (pintype "passive"))
      (node (ref "U0-C") (pin "36") (pinfunction "PA2_36") (pintype "bidirectional"))
    )
    (net (code "33") (name "MISO-1") (class "Default")
      (node (ref "J2-CS") (pin "2") (pinfunction "2_2") (pintype "passive"))
      (node (ref "U0-C") (pin "42") (pinfunction "PA6_42") (pintype "bidirectional"))
    )
    (net (code "34") (name "MISO-3") (class "Default")
      (node (ref "U0-C") (pin "112") (pinfunction "PC11_112") (pintype "bidirectional"))
      (node (ref "U1-C") (pin "2") (pinfunction "SO/IO1_2") (pintype "bidirectional"))
    )
    (net (code "35") (name "MOSI-1") (class "Default")
      (node (ref "J2-CS") (pin "3") (pinfunction "3_3") (pintype "passive"))
      (node (ref "U0-C") (pin "43") (pinfunction "PA7_43") (pintype "bidirectional"))
    )
    (net (code "36") (name "MOSI-3") (class "Default")
      (node (ref "U0-C") (pin "113") (pinfunction "PC12_113") (pintype "bidirectional"))
      (node (ref "U1-C") (pin "4") (pinfunction "SI/IO0_4") (pintype "bidirectional"))
    )
    (net (code "37") (name "NRST") (class "Default")
      (node (ref "C15-0C") (pin "1") (pinfunction "1_1") (pintype "passive"))
      (node (ref "R2-J1C") (pin "2") (pinfunction "2_2") (pintype "passive"))
      (node (ref "S1-0C") (pin "1") (pinfunction "S_1") (pintype "passive"))
      (node (ref "S1-0C") (pin "2") (pinfunction "S1_2") (pintype "passive"))
      (node (ref "U0-C") (pin "25") (pinfunction "NRST_25") (pintype "input"))
    )
    (net (code "38") (name "Net-(D0A-C-PadA)") (class "Default")
      (node (ref "D0A-C") (pin "A") (pinfunction "A_A") (pintype "passive"))
      (node (ref "R0A-C") (pin "2") (pinfunction "2_2") (pintype "passive"))
    )
    (net (code "39") (name "Net-(D0B-C-PadA)") (class "Default")
      (node (ref "D0B-C") (pin "A") (pinfunction "A_A") (pintype "passive"))
      (node (ref "R0B-C") (pin "2") (pinfunction "2_2") (pintype "passive"))
    )
    (net (code "40") (name "Net-(D0C-C-PadA)") (class "Default")
      (node (ref "D0C-C") (pin "A") (pinfunction "A_A") (pintype "passive"))
      (node (ref "R0C-C") (pin "2") (pinfunction "2_2") (pintype "passive"))
    )
    (net (code "41") (name "Net-(D1-LS1C-PadC)") (class "Default")
      (node (ref "D1-LS1C") (pin "C") (pinfunction "C_C") (pintype "passive"))
      (node (ref "R1-LS1C") (pin "2") (pinfunction "2_2") (pintype "passive"))
    )
    (net (code "42") (name "Net-(D1A-C-PadA)") (class "Default")
      (node (ref "D1A-C") (pin "A") (pinfunction "A_A") (pintype "passive"))
      (node (ref "R1A-C") (pin "2") (pinfunction "2_2") (pintype "passive"))
    )
    (net (code "43") (name "Net-(D1B-C-PadA)") (class "Default")
      (node (ref "D1B-C") (pin "A") (pinfunction "A_A") (pintype "passive"))
      (node (ref "R1B-C") (pin "2") (pinfunction "2_2") (pintype "passive"))
    )
    (net (code "44") (name "Net-(D2A-C-PadA)") (class "Default")
      (node (ref "D2A-C") (pin "A") (pinfunction "A_A") (pintype "passive"))
      (node (ref "R2A-C") (pin "2") (pinfunction "2_2") (pintype "passive"))
    )
    (net (code "45") (name "Net-(D2B-C-PadA)") (class "Default")
      (node (ref "D2B-C") (pin "A") (pinfunction "A_A") (pintype "passive"))
      (node (ref "R2B-C") (pin "2") (pinfunction "2_2") (pintype "passive"))
    )
    (net (code "46") (name "Net-(D3-C-PadA)") (class "Default")
      (node (ref "D3-C") (pin "A") (pinfunction "A_A") (pintype "passive"))
      (node (ref "R3-C") (pin "2") (pinfunction "2_2") (pintype "passive"))
    )
    (net (code "47") (name "Net-(D4-C-PadA)") (class "Default")
      (node (ref "D4-C") (pin "A") (pinfunction "A_A") (pintype "passive"))
      (node (ref "R4-C") (pin "2") (pinfunction "2_2") (pintype "passive"))
    )
    (net (code "48") (name "Net-(D5-C-PadA)") (class "Default")
      (node (ref "D5-C") (pin "A") (pinfunction "A_A") (pintype "passive"))
      (node (ref "R5-C") (pin "2") (pinfunction "2_2") (pintype "passive"))
    )
    (net (code "49") (name "Net-(D6-C-PadA)") (class "Default")
      (node (ref "D6-C") (pin "A") (pinfunction "A_A") (pintype "passive"))
      (node (ref "R6-C") (pin "2") (pinfunction "2_2") (pintype "passive"))
    )
    (net (code "50") (name "Net-(J1-C-Pad2)") (class "Default")
      (node (ref "J1-C") (pin "2") (pinfunction "2_2") (pintype "passive"))
      (node (ref "R4-J1C") (pin "1") (pinfunction "1_1") (pintype "passive"))
    )
    (net (code "51") (name "Net-(J1-C-Pad3)") (class "Default")
      (node (ref "J1-C") (pin "3") (pinfunction "3_3") (pintype "passive"))
      (node (ref "R3-J1C") (pin "1") (pinfunction "1_1") (pintype "passive"))
    )
    (net (code "52") (name "Net-(J1-C-Pad5)") (class "Default")
      (node (ref "J1-C") (pin "5") (pinfunction "5_5") (pintype "passive"))
      (node (ref "R1-J1C") (pin "1") (pinfunction "1_1") (pintype "passive"))
    )
    (net (code "53") (name "Net-(J1-C-Pad6)") (class "Default")
      (node (ref "J1-C") (pin "6") (pinfunction "6_6") (pintype "passive"))
      (node (ref "R2-J1C") (pin "1") (pinfunction "1_1") (pintype "passive"))
    )
    (net (code "54") (name "Net-(J2-C-D+)") (class "Default")
      (node (ref "J2-C") (pin "3") (pinfunction "D+_3") (pintype "bidirectional"))
      (node (ref "R2-J2C") (pin "1") (pinfunction "1_1") (pintype "passive"))
    )
    (net (code "55") (name "Net-(J2-C-D-)") (class "Default")
      (node (ref "J2-C") (pin "2") (pinfunction "D-_2") (pintype "bidirectional"))
      (node (ref "R1-J2C") (pin "1") (pinfunction "1_1") (pintype "passive"))
    )
    (net (code "56") (name "Net-(LS1-C-PadV+)") (class "Default")
      (node (ref "LS1-C") (pin "V+") (pinfunction "V+_V+") (pintype "bidirectional"))
      (node (ref "VR1-LS1C") (pin "S") (pinfunction "S_S") (pintype "passive"))
    )
    (net (code "57") (name "Net-(Q1-LS1C-C)") (class "Default")
      (node (ref "LS1-C") (pin "V-") (pinfunction "V-_V-") (pintype "bidirectional"))
      (node (ref "Q1-LS1C") (pin "2") (pinfunction "C_2") (pintype "passive"))
      (node (ref "R1-LS1C") (pin "1") (pinfunction "1_1") (pintype "passive"))
    )
    (net (code "58") (name "Net-(R3-LS1C-Pad2)") (class "Default")
      (node (ref "R3-LS1C") (pin "2") (pinfunction "2_2") (pintype "passive"))
      (node (ref "VR1-LS1C") (pin "E") (pinfunction "E_E") (pintype "passive"))
    )
    (net (code "59") (name "Net-(U0-C-BOOT0)") (class "Default")
      (node (ref "R1-0C") (pin "1") (pinfunction "1_1") (pintype "passive"))
      (node (ref "U0-C") (pin "138") (pinfunction "BOOT0_138") (pintype "bidirectional"))
    )
    (net (code "60") (name "Net-(U0-C-VCAP_1)") (class "Default")
      (node (ref "C16-0C") (pin "1") (pinfunction "1_1") (pintype "passive"))
      (node (ref "U0-C") (pin "71") (pinfunction "VCAP_1_71") (pintype "bidirectional"))
    )
    (net (code "61") (name "Net-(U0-C-VCAP_2)") (class "Default")
      (node (ref "C17-0C") (pin "1") (pinfunction "1_1") (pintype "passive"))
      (node (ref "U0-C") (pin "106") (pinfunction "VCAP_2_106") (pintype "bidirectional"))
    )
    (net (code "62") (name "Net-(U2-C-ADDR)") (class "Default")
      (node (ref "R3-2C") (pin "2") (pinfunction "2_2") (pintype "passive"))
      (node (ref "U2-C") (pin "1") (pinfunction "ADDR_1") (pintype "bidirectional"))
    )
    (net (code "63") (name "OSC_IN") (class "Default")
      (node (ref "C1-Y1C") (pin "1") (pinfunction "1_1") (pintype "passive"))
      (node (ref "U0-C") (pin "23") (pinfunction "PH0_23") (pintype "bidirectional"))
      (node (ref "Y1-C") (pin "P$2") (pinfunction "2_P$2") (pintype "passive"))
    )
    (net (code "64") (name "OSC_OUT") (class "Default")
      (node (ref "C2-Y1C") (pin "1") (pinfunction "1_1") (pintype "passive"))
      (node (ref "U0-C") (pin "24") (pinfunction "PH1_24") (pintype "bidirectional"))
      (node (ref "Y1-C") (pin "P$1") (pinfunction "1_P$1") (pintype "passive"))
    )
    (net (code "65") (name "RTS") (class "Default")
      (node (ref "J1-CP") (pin "1") (pinfunction "1_1") (pintype "passive"))
      (node (ref "U0-C") (pin "35") (pinfunction "PA1_35") (pintype "bidirectional"))
    )
    (net (code "66") (name "SCL-1") (class "Default")
      (node (ref "R2-2C") (pin "2") (pinfunction "2_2") (pintype "passive"))
      (node (ref "U0-C") (pin "100") (pinfunction "PA8_100") (pintype "bidirectional"))
      (node (ref "U2-C") (pin "10") (pinfunction "SCL_10") (pintype "bidirectional"))
    )
    (net (code "67") (name "SDA-1") (class "Default")
      (node (ref "R1-2C") (pin "2") (pinfunction "2_2") (pintype "passive"))
      (node (ref "U0-C") (pin "99") (pinfunction "PC9_99") (pintype "bidirectional"))
      (node (ref "U2-C") (pin "9") (pinfunction "SDA_9") (pintype "bidirectional"))
    )
    (net (code "68") (name "SENSE_A") (class "Default")
      (node (ref "J3-CP") (pin "1") (pinfunction "1_1") (pintype "passive"))
      (node (ref "U0-C") (pin "18") (pinfunction "PF6_18") (pintype "bidirectional"))
      (node (ref "U2-C") (pin "4") (pinfunction "AIN0_4") (pintype "bidirectional"))
    )
    (net (code "69") (name "SENSE_B") (class "Default")
      (node (ref "J3-CP") (pin "2") (pinfunction "2_2") (pintype "passive"))
      (node (ref "U0-C") (pin "19") (pinfunction "PF7_19") (pintype "bidirectional"))
      (node (ref "U2-C") (pin "5") (pinfunction "AIN1_5") (pintype "bidirectional"))
    )
    (net (code "70") (name "SENSE_C") (class "Default")
      (node (ref "J3-CP") (pin "3") (pinfunction "3_3") (pintype "passive"))
      (node (ref "U0-C") (pin "20") (pinfunction "PF8_20") (pintype "bidirectional"))
      (node (ref "U2-C") (pin "6") (pinfunction "AIN2_6") (pintype "bidirectional"))
    )
    (net (code "71") (name "SENSE_D") (class "Default")
      (node (ref "J3-CP") (pin "4") (pinfunction "4_4") (pintype "passive"))
      (node (ref "U0-C") (pin "21") (pinfunction "PF9_21") (pintype "bidirectional"))
      (node (ref "U2-C") (pin "7") (pinfunction "AIN3_7") (pintype "bidirectional"))
    )
    (net (code "72") (name "SENSOR-ERROR") (class "Default")
      (node (ref "J3-CS") (pin "2") (pinfunction "2_2") (pintype "passive"))
      (node (ref "U0-C") (pin "64") (pinfunction "PE11_64") (pintype "bidirectional"))
    )
    (net (code "73") (name "SENSOR-NOMINAL") (class "Default")
      (node (ref "J3-CS") (pin "1") (pinfunction "1_1") (pintype "passive"))
      (node (ref "U0-C") (pin "63") (pinfunction "PE10_63") (pintype "bidirectional"))
    )
    (net (code "74") (name "STORAGE-ERROR") (class "Default")
      (node (ref "R5-C") (pin "1") (pinfunction "1_1") (pintype "passive"))
      (node (ref "U0-C") (pin "58") (pinfunction "PE7_58") (pintype "bidirectional"))
    )
    (net (code "75") (name "SWCLK") (class "Default")
      (node (ref "R4-J1C") (pin "2") (pinfunction "2_2") (pintype "passive"))
      (node (ref "U0-C") (pin "109") (pinfunction "PA14_109") (pintype "bidirectional"))
    )
    (net (code "76") (name "SWDIO") (class "Default")
      (node (ref "R3-J1C") (pin "2") (pinfunction "2_2") (pintype "passive"))
      (node (ref "U0-C") (pin "105") (pinfunction "PA13_105") (pintype "bidirectional"))
    )
    (net (code "77") (name "SWO") (class "Default")
      (node (ref "R1-J1C") (pin "2") (pinfunction "2_2") (pintype "passive"))
      (node (ref "U0-C") (pin "133") (pinfunction "PB3_133") (pintype "bidirectional"))
    )
    (net (code "78") (name "U1S-CHECK") (class "Default")
      (node (ref "J3-CS") (pin "3") (pinfunction "3_3") (pintype "passive"))
      (node (ref "U0-C") (pin "65") (pinfunction "PE12_65") (pintype "bidirectional"))
    )
    (net (code "79") (name "U2S-CHECK") (class "Default")
      (node (ref "J3-CS") (pin "4") (pinfunction "4_4") (pintype "passive"))
      (node (ref "U0-C") (pin "66") (pinfunction "PE13_66") (pintype "bidirectional"))
    )
    (net (code "80") (name "U2S-ST") (class "Default")
      (node (ref "J3-CS") (pin "7") (pinfunction "7_7") (pintype "passive"))
      (node (ref "U0-C") (pin "69") (pinfunction "PB10_69") (pintype "bidirectional"))
    )
    (net (code "81") (name "U3S-CHECK") (class "Default")
      (node (ref "J3-CS") (pin "5") (pinfunction "5_5") (pintype "passive"))
      (node (ref "U0-C") (pin "67") (pinfunction "PE14_67") (pintype "bidirectional"))
    )
    (net (code "82") (name "U4S-CHECK") (class "Default")
      (node (ref "J3-CS") (pin "6") (pinfunction "6_6") (pintype "passive"))
      (node (ref "U0-C") (pin "68") (pinfunction "PE15_68") (pintype "bidirectional"))
    )
    (net (code "83") (name "US2-STATUS") (class "Default")
      (node (ref "J3-CS") (pin "8") (pinfunction "8_8") (pintype "passive"))
      (node (ref "U0-C") (pin "70") (pinfunction "PB11_70") (pintype "bidirectional"))
    )
    (net (code "84") (name "VDDA") (class "Default")
      (node (ref "FB1-0C") (pin "2") (pinfunction "2_2") (pintype "bidirectional"))
      (node (ref "U0-C") (pin "32") (pinfunction "VREF+_32") (pintype "input"))
      (node (ref "U0-C") (pin "33") (pinfunction "VDDA_33") (pintype "power_in"))
    )
    (net (code "85") (name "VUSB") (class "Default")
      (node (ref "J2-C") (pin "1") (pinfunction "VBUS_1") (pintype "power_in"))
      (node (ref "JP-CP") (pin "4") (pinfunction "4_4") (pintype "passive"))
    )
    (net (code "86") (name "WP") (class "Default")
      (node (ref "U0-C") (pin "115") (pinfunction "PD1_115") (pintype "bidirectional"))
      (node (ref "U1-C") (pin "3") (pinfunction "~{WP}/IO2_3") (pintype "bidirectional"))
    )
    (net (code "87") (name "unconnected-(JP-CS-Pad4)") (class "Default")
      (node (ref "JP-CS") (pin "4") (pinfunction "4_4") (pintype "passive"))
    )
    (net (code "88") (name "unconnected-(S0-0C-P1-Pad4)") (class "Default")
      (node (ref "S0-0C") (pin "4") (pinfunction "P1_4") (pintype "passive"))
    )
    (net (code "89") (name "unconnected-(S0-0C-S1-Pad2)") (class "Default")
      (node (ref "S0-0C") (pin "2") (pinfunction "S1_2") (pintype "passive"))
    )
    (net (code "90") (name "unconnected-(U0-C-PA4-Pad40)") (class "Default")
      (node (ref "U0-C") (pin "40") (pinfunction "PA4_40") (pintype "bidirectional"))
    )
    (net (code "91") (name "unconnected-(U0-C-PA9-Pad101)") (class "Default")
      (node (ref "U0-C") (pin "101") (pinfunction "PA9_101") (pintype "bidirectional"))
    )
    (net (code "92") (name "unconnected-(U0-C-PA15-Pad110)") (class "Default")
      (node (ref "U0-C") (pin "110") (pinfunction "PA15_110") (pintype "bidirectional"))
    )
    (net (code "93") (name "unconnected-(U0-C-PB2-Pad48)") (class "Default")
      (node (ref "U0-C") (pin "48") (pinfunction "PB2_48") (pintype "bidirectional"))
    )
    (net (code "94") (name "unconnected-(U0-C-PB4-Pad134)") (class "Default")
      (node (ref "U0-C") (pin "134") (pinfunction "PB4_134") (pintype "bidirectional"))
    )
    (net (code "95") (name "unconnected-(U0-C-PB5-Pad135)") (class "Default")
      (node (ref "U0-C") (pin "135") (pinfunction "PB5_135") (pintype "bidirectional"))
    )
    (net (code "96") (name "unconnected-(U0-C-PB6-Pad136)") (class "Default")
      (node (ref "U0-C") (pin "136") (pinfunction "PB6_136") (pintype "bidirectional"))
    )
    (net (code "97") (name "unconnected-(U0-C-PB7-Pad137)") (class "Default")
      (node (ref "U0-C") (pin "137") (pinfunction "PB7_137") (pintype "bidirectional"))
    )
    (net (code "98") (name "unconnected-(U0-C-PB8-Pad139)") (class "Default")
      (node (ref "U0-C") (pin "139") (pinfunction "PB8_139") (pintype "bidirectional"))
    )
    (net (code "99") (name "unconnected-(U0-C-PB9-Pad140)") (class "Default")
      (node (ref "U0-C") (pin "140") (pinfunction "PB9_140") (pintype "bidirectional"))
    )
    (net (code "100") (name "unconnected-(U0-C-PB12-Pad73)") (class "Default")
      (node (ref "U0-C") (pin "73") (pinfunction "PB12_73") (pintype "bidirectional"))
    )
    (net (code "101") (name "unconnected-(U0-C-PB13-Pad74)") (class "Default")
      (node (ref "U0-C") (pin "74") (pinfunction "PB13_74") (pintype "bidirectional"))
    )
    (net (code "102") (name "unconnected-(U0-C-PB14-Pad75)") (class "Default")
      (node (ref "U0-C") (pin "75") (pinfunction "PB14_75") (pintype "bidirectional"))
    )
    (net (code "103") (name "unconnected-(U0-C-PB15-Pad76)") (class "Default")
      (node (ref "U0-C") (pin "76") (pinfunction "PB15_76") (pintype "bidirectional"))
    )
    (net (code "104") (name "unconnected-(U0-C-PC0-Pad26)") (class "Default")
      (node (ref "U0-C") (pin "26") (pinfunction "PC0_26") (pintype "bidirectional"))
    )
    (net (code "105") (name "unconnected-(U0-C-PC1-Pad27)") (class "Default")
      (node (ref "U0-C") (pin "27") (pinfunction "PC1_27") (pintype "bidirectional"))
    )
    (net (code "106") (name "unconnected-(U0-C-PC2-Pad28)") (class "Default")
      (node (ref "U0-C") (pin "28") (pinfunction "PC2_28") (pintype "bidirectional"))
    )
    (net (code "107") (name "unconnected-(U0-C-PC3-Pad29)") (class "Default")
      (node (ref "U0-C") (pin "29") (pinfunction "PC3_29") (pintype "bidirectional"))
    )
    (net (code "108") (name "unconnected-(U0-C-PC13-Pad7)") (class "Default")
      (node (ref "U0-C") (pin "7") (pinfunction "PC13_7") (pintype "bidirectional"))
    )
    (net (code "109") (name "unconnected-(U0-C-PC14-Pad8)") (class "Default")
      (node (ref "U0-C") (pin "8") (pinfunction "PC14_8") (pintype "bidirectional"))
    )
    (net (code "110") (name "unconnected-(U0-C-PC15-Pad9)") (class "Default")
      (node (ref "U0-C") (pin "9") (pinfunction "PC15_9") (pintype "bidirectional"))
    )
    (net (code "111") (name "unconnected-(U0-C-PD3-Pad117)") (class "Default")
      (node (ref "U0-C") (pin "117") (pinfunction "PD3_117") (pintype "bidirectional"))
    )
    (net (code "112") (name "unconnected-(U0-C-PD4-Pad118)") (class "Default")
      (node (ref "U0-C") (pin "118") (pinfunction "PD4_118") (pintype "bidirectional"))
    )
    (net (code "113") (name "unconnected-(U0-C-PD5-Pad119)") (class "Default")
      (node (ref "U0-C") (pin "119") (pinfunction "PD5_119") (pintype "bidirectional"))
    )
    (net (code "114") (name "unconnected-(U0-C-PD6-Pad122)") (class "Default")
      (node (ref "U0-C") (pin "122") (pinfunction "PD6_122") (pintype "bidirectional"))
    )
    (net (code "115") (name "unconnected-(U0-C-PD7-Pad123)") (class "Default")
      (node (ref "U0-C") (pin "123") (pinfunction "PD7_123") (pintype "bidirectional"))
    )
    (net (code "116") (name "unconnected-(U0-C-PD8-Pad77)") (class "Default")
      (node (ref "U0-C") (pin "77") (pinfunction "PD8_77") (pintype "bidirectional"))
    )
    (net (code "117") (name "unconnected-(U0-C-PD9-Pad78)") (class "Default")
      (node (ref "U0-C") (pin "78") (pinfunction "PD9_78") (pintype "bidirectional"))
    )
    (net (code "118") (name "unconnected-(U0-C-PD10-Pad79)") (class "Default")
      (node (ref "U0-C") (pin "79") (pinfunction "PD10_79") (pintype "bidirectional"))
    )
    (net (code "119") (name "unconnected-(U0-C-PD11-Pad80)") (class "Default")
      (node (ref "U0-C") (pin "80") (pinfunction "PD11_80") (pintype "bidirectional"))
    )
    (net (code "120") (name "unconnected-(U0-C-PD12-Pad81)") (class "Default")
      (node (ref "U0-C") (pin "81") (pinfunction "PD12_81") (pintype "bidirectional"))
    )
    (net (code "121") (name "unconnected-(U0-C-PD13-Pad82)") (class "Default")
      (node (ref "U0-C") (pin "82") (pinfunction "PD13_82") (pintype "bidirectional"))
    )
    (net (code "122") (name "unconnected-(U0-C-PD14-Pad85)") (class "Default")
      (node (ref "U0-C") (pin "85") (pinfunction "PD14_85") (pintype "bidirectional"))
    )
    (net (code "123") (name "unconnected-(U0-C-PD15-Pad86)") (class "Default")
      (node (ref "U0-C") (pin "86") (pinfunction "PD15_86") (pintype "bidirectional"))
    )
    (net (code "124") (name "unconnected-(U0-C-PE0-Pad141)") (class "Default")
      (node (ref "U0-C") (pin "141") (pinfunction "PE0_141") (pintype "bidirectional"))
    )
    (net (code "125") (name "unconnected-(U0-C-PE1-Pad142)") (class "Default")
      (node (ref "U0-C") (pin "142") (pinfunction "PE1_142") (pintype "bidirectional"))
    )
    (net (code "126") (name "unconnected-(U0-C-PE3-Pad2)") (class "Default")
      (node (ref "U0-C") (pin "2") (pinfunction "PE3_2") (pintype "bidirectional"))
    )
    (net (code "127") (name "unconnected-(U0-C-PE4-Pad3)") (class "Default")
      (node (ref "U0-C") (pin "3") (pinfunction "PE4_3") (pintype "bidirectional"))
    )
    (net (code "128") (name "unconnected-(U0-C-PE5-Pad4)") (class "Default")
      (node (ref "U0-C") (pin "4") (pinfunction "PE5_4") (pintype "bidirectional"))
    )
    (net (code "129") (name "unconnected-(U0-C-PE6-Pad5)") (class "Default")
      (node (ref "U0-C") (pin "5") (pinfunction "PE6_5") (pintype "bidirectional"))
    )
    (net (code "130") (name "unconnected-(U0-C-PE9-Pad60)") (class "Default")
      (node (ref "U0-C") (pin "60") (pinfunction "PE9_60") (pintype "bidirectional"))
    )
    (net (code "131") (name "unconnected-(U0-C-PF0-Pad10)") (class "Default")
      (node (ref "U0-C") (pin "10") (pinfunction "PF0_10") (pintype "bidirectional"))
    )
    (net (code "132") (name "unconnected-(U0-C-PF5-Pad15)") (class "Default")
      (node (ref "U0-C") (pin "15") (pinfunction "PF5_15") (pintype "bidirectional"))
    )
    (net (code "133") (name "unconnected-(U0-C-PF10-Pad22)") (class "Default")
      (node (ref "U0-C") (pin "22") (pinfunction "PF10_22") (pintype "bidirectional"))
    )
    (net (code "134") (name "unconnected-(U0-C-PF11-Pad49)") (class "Default")
      (node (ref "U0-C") (pin "49") (pinfunction "PF11_49") (pintype "bidirectional"))
    )
    (net (code "135") (name "unconnected-(U0-C-PF12-Pad50)") (class "Default")
      (node (ref "U0-C") (pin "50") (pinfunction "PF12_50") (pintype "bidirectional"))
    )
    (net (code "136") (name "unconnected-(U0-C-PG2-Pad87)") (class "Default")
      (node (ref "U0-C") (pin "87") (pinfunction "PG2_87") (pintype "bidirectional"))
    )
    (net (code "137") (name "unconnected-(U0-C-PG3-Pad88)") (class "Default")
      (node (ref "U0-C") (pin "88") (pinfunction "PG3_88") (pintype "bidirectional"))
    )
    (net (code "138") (name "unconnected-(U0-C-PG5-Pad90)") (class "Default")
      (node (ref "U0-C") (pin "90") (pinfunction "PG5_90") (pintype "bidirectional"))
    )
    (net (code "139") (name "unconnected-(U0-C-PG6-Pad91)") (class "Default")
      (node (ref "U0-C") (pin "91") (pinfunction "PG6_91") (pintype "bidirectional"))
    )
    (net (code "140") (name "unconnected-(U0-C-PG7-Pad92)") (class "Default")
      (node (ref "U0-C") (pin "92") (pinfunction "PG7_92") (pintype "bidirectional"))
    )
    (net (code "141") (name "unconnected-(U0-C-PG8-Pad93)") (class "Default")
      (node (ref "U0-C") (pin "93") (pinfunction "PG8_93") (pintype "bidirectional"))
    )
    (net (code "142") (name "unconnected-(U0-C-PG9-Pad124)") (class "Default")
      (node (ref "U0-C") (pin "124") (pinfunction "PG9_124") (pintype "bidirectional"))
    )
    (net (code "143") (name "unconnected-(U0-C-PG10-Pad125)") (class "Default")
      (node (ref "U0-C") (pin "125") (pinfunction "PG10_125") (pintype "bidirectional"))
    )
    (net (code "144") (name "unconnected-(U0-C-PG11-Pad126)") (class "Default")
      (node (ref "U0-C") (pin "126") (pinfunction "PG11_126") (pintype "bidirectional"))
    )
    (net (code "145") (name "unconnected-(U0-C-PG12-Pad127)") (class "Default")
      (node (ref "U0-C") (pin "127") (pinfunction "PG12_127") (pintype "bidirectional"))
    )
    (net (code "146") (name "unconnected-(U0-C-PG13-Pad128)") (class "Default")
      (node (ref "U0-C") (pin "128") (pinfunction "PG13_128") (pintype "bidirectional"))
    )
    (net (code "147") (name "unconnected-(U0-C-PG14-Pad129)") (class "Default")
      (node (ref "U0-C") (pin "129") (pinfunction "PG14_129") (pintype "bidirectional"))
    )
    (net (code "148") (name "unconnected-(U0-C-PG15-Pad132)") (class "Default")
      (node (ref "U0-C") (pin "132") (pinfunction "PG15_132") (pintype "bidirectional"))
    )
    (net (code "149") (name "unconnected-(U1-C-EP-Pad9)") (class "Default")
      (node (ref "U1-C") (pin "9") (pinfunction "EP_9") (pintype "bidirectional"))
    )
  )
)
